# 14-Power-P1V8.net
KiCad netlist of a schematic drawn in Altium Designer
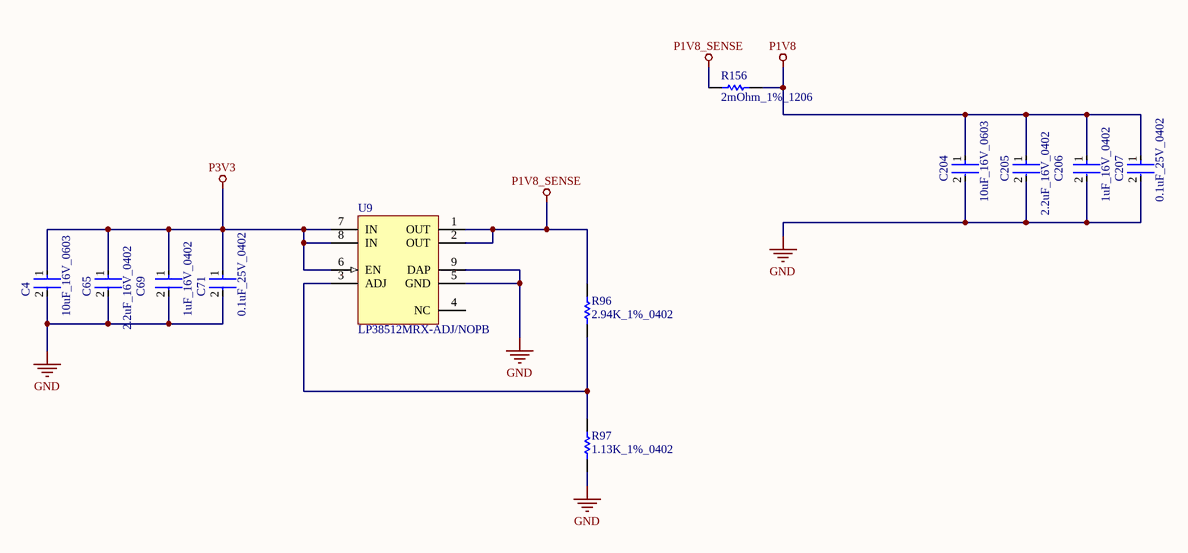
[diagram p0: 14-Power-P1V8.SchDoc]

(export (version "E")
  (design (tool "Eeschema 10.0.6"))
  (components
    (comp (ref "C4")
      (value "10uF_16V_0603")
      (footprint "FP-0603-L_1_6_0_2-W_0_8_0-MFG")
      (description "Multilayer Ceramic Capacitor 10uF 16V X5R 20% SMD 0603 T/R")
      (fields (field (name "TOLERANCE") "20%"))
      (libsource (lib "Altium Content Vault") (part "b4654b650e69147ec39a6b967a45e02"))
    )
    (comp (ref "C65")
      (value "2.2uF_16V_0402")
      (footprint "FP-C1005-050-0_05-IPC_A")
      (description "Multilayer Ceramic Capacitors 2.2μF ±10% 16V X5R SMD 0402")
      (fields (field (name "TOLERANCE") "10%"))
      (libsource (lib "Altium Content Vault") (part "b4654b650e69147ec39a6b967a45e02"))
    )
    (comp (ref "C69")
      (value "1uF_16V_0402")
      (footprint "FP-0402-L_1_0_0_05-W_0_5-IPC_A")
      (description "None")
      (fields (field (name "TOLERANCE") "10%"))
      (libsource (lib "Altium Content Vault") (part "b4654b650e69147ec39a6b967a45e02"))
    )
    (comp (ref "C71")
      (value "0.1uF_25V_0402")
      (footprint "FP-0402-L_1_0_1-W_0_5_0_1-IPC_C")
      (description "General Purpose Ceramic Capacitor, 0402, 100nF, 10%, X7R, 15%, 25V")
      (fields (field (name "VOLTAGE") "25V") (field (name "TOLERANCE") "10%"))
      (libsource (lib "Altium Content Vault") (part "b4654b650e69147ec39a6b967a45e02"))
    )
    (comp (ref "C204")
      (value "10uF_16V_0603")
      (footprint "FP-0603-L_1_6_0_2-W_0_8_0-MFG")
      (description "Multilayer Ceramic Capacitor 10uF 16V X5R 20% SMD 0603 T/R")
      (fields (field (name "TOLERANCE") "20%"))
      (libsource (lib "Altium Content Vault") (part "b4654b650e69147ec39a6b967a45e02"))
    )
    (comp (ref "C205")
      (value "2.2uF_16V_0402")
      (footprint "FP-C1005-050-0_05-IPC_A")
      (description "Multilayer Ceramic Capacitors 2.2μF ±10% 16V X5R SMD 0402")
      (fields (field (name "TOLERANCE") "10%"))
      (libsource (lib "Altium Content Vault") (part "b4654b650e69147ec39a6b967a45e02"))
    )
    (comp (ref "C206")
      (value "1uF_16V_0402")
      (footprint "FP-0402-L_1_0_0_05-W_0_5-IPC_A")
      (description "None")
      (fields (field (name "TOLERANCE") "10%"))
      (libsource (lib "Altium Content Vault") (part "b4654b650e69147ec39a6b967a45e02"))
    )
    (comp (ref "C207")
      (value "0.1uF_25V_0402")
      (footprint "FP-0402-L_1_0_1-W_0_5_0_1-IPC_C")
      (description "General Purpose Ceramic Capacitor, 0402, 100nF, 10%, X7R, 15%, 25V")
      (fields (field (name "VOLTAGE") "25V") (field (name "TOLERANCE") "10%"))
      (libsource (lib "Altium Content Vault") (part "b4654b650e69147ec39a6b967a45e02"))
    )
    (comp (ref "R96")
      (value "2.94K_1%_0402")
      (footprint "RESC1005X40X25ML05T10")
      (fields (field (name "MANUFACTURER") "Yageo") (field (name "PART NUMBER") "RC0402FR-072K94L"))
      (libsource (lib "Altium Content Vault") (part "RES"))
    )
    (comp (ref "R97")
      (value "1.13K_1%_0402")
      (footprint "RESC1005X40X25NL05T05")
      (fields (field (name "MANUFACTURER") "Panasonic") (field (name "PART NUMBER") "ERJ-2RKF1131X"))
      (libsource (lib "Altium Content Vault") (part "RES"))
    )
    (comp (ref "R156")
      (value "2mOhm_1%_1206")
      (footprint "RESC3216X89X64NL25T25")
      (fields (field (name "MANUFACTURER") "Vishay Dale") (field (name "PART NUMBER") "WSL12062L000FEA18"))
      (libsource (lib "Altium Content Vault") (part "RES"))
    )
    (comp (ref "U9")
      (value "LP38512MRX-ADJ/NOPB")
      (footprint "MRA08B_M")
      (description "1.5A Fast-Transient Response Adjustable Low-Dropout Linear Voltage Regulator, 8-pin PSOP, Pb-Free")
      (fields (field (name "MANUFACTURER") "National Semiconductor"))
      (libsource (lib "Altium Content Vault") (part "PM-REG-LP38512MR-IL9"))
    )
  )
  (nets
    (net (code "1") (name "GND") (class "Default")
      (node (ref "C204") (pin "2") (pinfunction "2_2") (pintype "passive"))
      (node (ref "C205") (pin "2") (pinfunction "2_2") (pintype "passive"))
      (node (ref "C206") (pin "2") (pinfunction "2_2") (pintype "passive"))
      (node (ref "C207") (pin "2") (pinfunction "2_2") (pintype "passive"))
      (node (ref "C4") (pin "2") (pinfunction "2_2") (pintype "passive"))
      (node (ref "C65") (pin "2") (pinfunction "2_2") (pintype "passive"))
      (node (ref "C69") (pin "2") (pinfunction "2_2") (pintype "passive"))
      (node (ref "C71") (pin "2") (pinfunction "2_2") (pintype "passive"))
      (node (ref "R97") (pin "1") (pinfunction "1_1") (pintype "passive"))
      (node (ref "U9") (pin "5") (pinfunction "GND_5") (pintype "power_in"))
      (node (ref "U9") (pin "9") (pinfunction "DAP_9") (pintype "passive"))
    )
    (net (code "2") (name "Net-(U9-ADJ)") (class "Default")
      (node (ref "R96") (pin "1") (pinfunction "1_1") (pintype "passive"))
      (node (ref "R97") (pin "2") (pinfunction "2_2") (pintype "passive"))
      (node (ref "U9") (pin "3") (pinfunction "ADJ_3") (pintype "passive"))
    )
    (net (code "3") (name "P1V8") (class "Default")
      (node (ref "C204") (pin "1") (pinfunction "1_1") (pintype "passive"))
      (node (ref "C205") (pin "1") (pinfunction "1_1") (pintype "passive"))
      (node (ref "C206") (pin "1") (pinfunction "1_1") (pintype "passive"))
      (node (ref "C207") (pin "1") (pinfunction "1_1") (pintype "passive"))
      (node (ref "R156") (pin "2") (pinfunction "2_2") (pintype "passive"))
    )
    (net (code "4") (name "P1V8_SENSE") (class "Default")
      (node (ref "R156") (pin "1") (pinfunction "1_1") (pintype "passive"))
      (node (ref "R96") (pin "2") (pinfunction "2_2") (pintype "passive"))
      (node (ref "U9") (pin "1") (pinfunction "OUT_1") (pintype "power_in"))
      (node (ref "U9") (pin "2") (pinfunction "OUT_2") (pintype "power_in"))
    )
    (net (code "5") (name "P3V3") (class "Default")
      (node (ref "C4") (pin "1") (pinfunction "1_1") (pintype "passive"))
      (node (ref "C65") (pin "1") (pinfunction "1_1") (pintype "passive"))
      (node (ref "C69") (pin "1") (pinfunction "1_1") (pintype "passive"))
      (node (ref "C71") (pin "1") (pinfunction "1_1") (pintype "passive"))
      (node (ref "U9") (pin "6") (pinfunction "EN_6") (pintype "input"))
      (node (ref "U9") (pin "7") (pinfunction "IN_7") (pintype "power_in"))
      (node (ref "U9") (pin "8") (pinfunction "IN_8") (pintype "power_in"))
    )
    (net (code "6") (name "unconnected-(U9-NC-Pad4)") (class "Default")
      (node (ref "U9") (pin "4") (pinfunction "NC_4") (pintype "passive"))
    )
  )
)
